# mesure___acquisition.net
KiCad netlist of a schematic drawn in Altium Designer
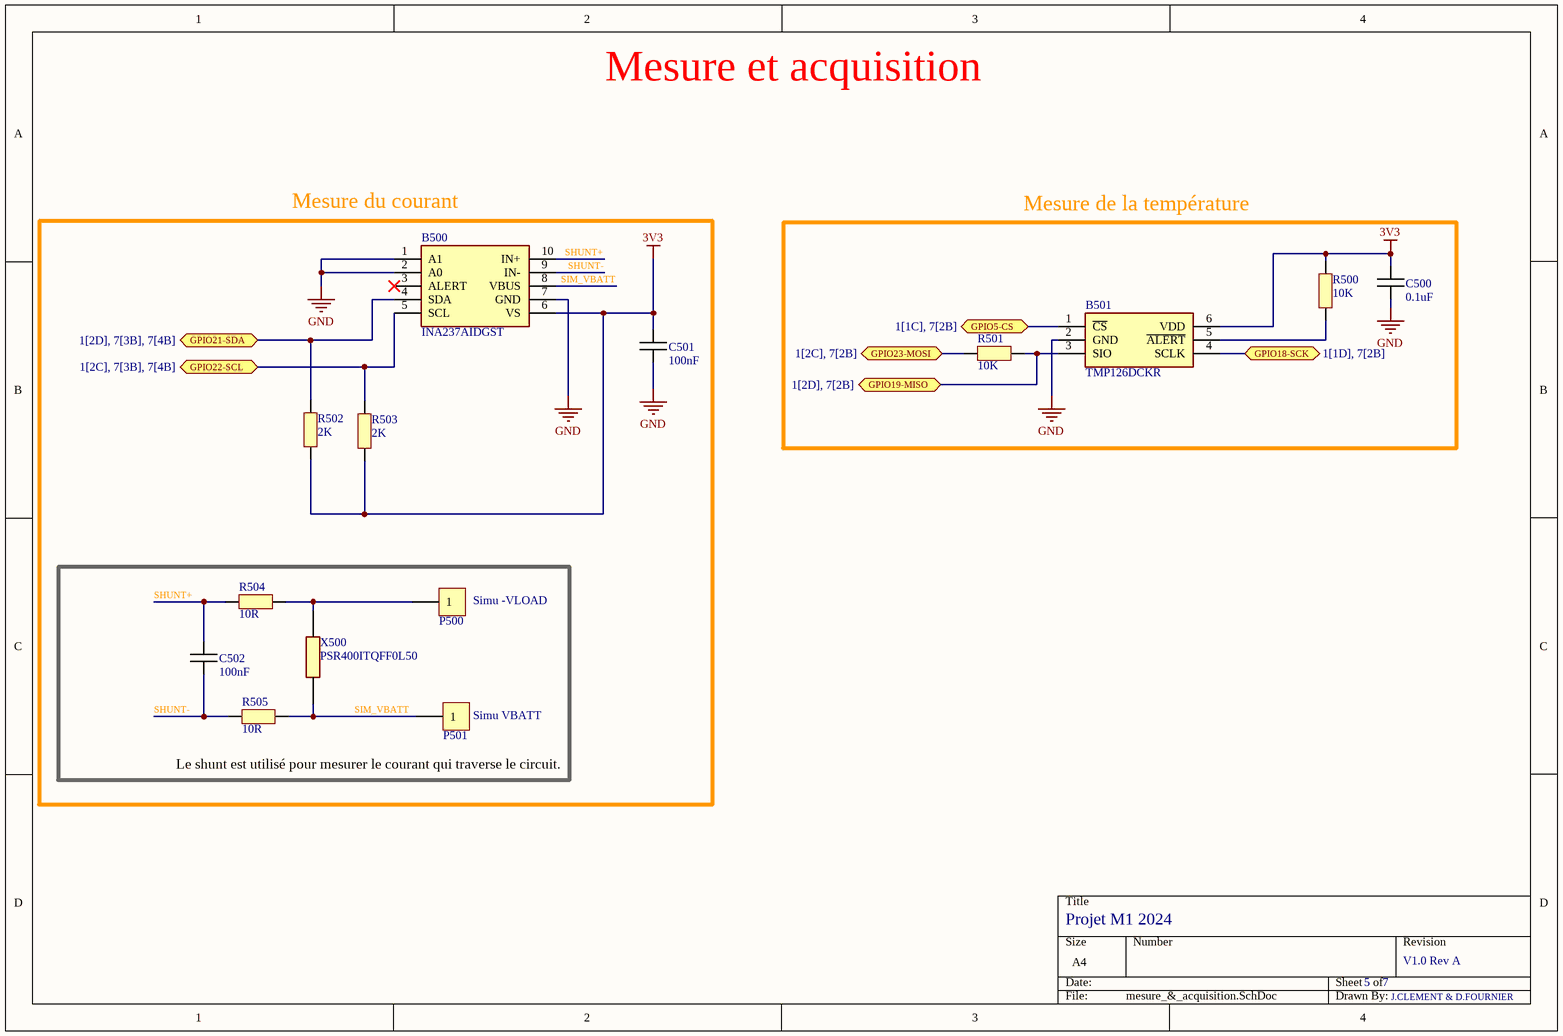
[diagram p0: mesure_&_acquisition.SchDoc]

(export (version "E")
  (design (tool "Eeschema 10.0.6"))
  (components
    (comp (ref "B500")
      (value "INA237AIDGST")
      (footprint "SOP50P490X110-10N")
      (fields (field (name "MOUSER PART NUMBER") "595-INA237AIDGST"))
      (libsource (lib "SCHLibrary") (part "INA237AIDGST"))
    )
    (comp (ref "B501")
      (value "TMP126DCKR")
      (footprint "SOT65P210X110-6N")
      (fields (field (name "MOUSER PART NUMBER") "595-TMP126DCKR"))
      (libsource (lib "SCHLibrary") (part "TMP126DCKR"))
    )
    (comp (ref "C500")
      (value "0.1uF")
      (footprint "CAPA_0603")
      (libsource (lib "SCHLibrary") (part "Capacitor"))
    )
    (comp (ref "C501")
      (value "100nF")
      (footprint "CAPA_0603")
      (libsource (lib "SCHLibrary") (part "Capacitor"))
    )
    (comp (ref "C502")
      (value "100nF")
      (footprint "CAPA_0603")
      (libsource (lib "SCHLibrary") (part "Capacitor"))
    )
    (comp (ref "P500")
      (value "Plage CMS 10x5")
      (footprint "Plage CMS 10x5")
      (description "Plage de report CMS 10x5mm")
      (libsource (lib "SCHLibrary") (part "Plage CMS 10x5"))
    )
    (comp (ref "P501")
      (value "Plage CMS 10x5")
      (footprint "Plage CMS 10x5")
      (description "Plage de report CMS 10x5mm")
      (libsource (lib "SCHLibrary") (part "Plage CMS 10x5"))
    )
    (comp (ref "R500") (value "10K") (footprint "RES_0603") (libsource (lib "SCHLibrary") (part "Resistor")))
    (comp (ref "R501") (value "10K") (footprint "RES_0603") (libsource (lib "") (part "Resistor_1")))
    (comp (ref "R502") (value "2K") (footprint "RES_0603") (libsource (lib "SCHLibrary") (part "Resistor")))
    (comp (ref "R503") (value "2K") (footprint "RES_0603") (libsource (lib "SCHLibrary") (part "Resistor")))
    (comp (ref "R504") (value "10R") (footprint "RES_0603") (libsource (lib "") (part "Resistor_1")))
    (comp (ref "R505") (value "10R") (footprint "RES_0603") (libsource (lib "") (part "Resistor_1")))
    (comp (ref "X500")
      (value "PSR400ITQFF0L50")
      (footprint "RESC10052X200N")
      (fields (field (name "MOUSER PART NUMBER") "755-PSR400ITQFF0L50"))
      (libsource (lib "SCHLibrary") (part "PSR400ITQFF0L50"))
    )
  )
  (nets
    (net (code "1") (name "/GPIO5-CS") (class "Default")
      (node (ref "B501") (pin "1") (pinfunction "~{CS}_1") (pintype "passive"))
    )
    (net (code "2") (name "/GPIO18-SCK") (class "Default")
      (node (ref "B501") (pin "4") (pinfunction "SCLK_4") (pintype "passive"))
    )
    (net (code "3") (name "/GPIO19-MISO") (class "Default")
      (node (ref "B501") (pin "3") (pinfunction "SIO_3") (pintype "passive"))
      (node (ref "R501") (pin "2") (pinfunction "2_2") (pintype "passive"))
    )
    (net (code "4") (name "/GPIO21-SDA") (class "Default")
      (node (ref "B500") (pin "4") (pinfunction "SDA_4") (pintype "passive"))
      (node (ref "R502") (pin "2") (pinfunction "2_2") (pintype "passive"))
    )
    (net (code "5") (name "/GPIO22-SCL") (class "Default")
      (node (ref "B500") (pin "5") (pinfunction "SCL_5") (pintype "passive"))
      (node (ref "R503") (pin "2") (pinfunction "2_2") (pintype "passive"))
    )
    (net (code "6") (name "/GPIO23-MOSI") (class "Default")
      (node (ref "R501") (pin "1") (pinfunction "1_1") (pintype "passive"))
    )
    (net (code "7") (name "/SHUNT+") (class "Default")
      (node (ref "B500") (pin "10") (pinfunction "IN+_10") (pintype "passive"))
      (node (ref "C502") (pin "1") (pinfunction "1_1") (pintype "passive"))
      (node (ref "R504") (pin "1") (pinfunction "1_1") (pintype "passive"))
    )
    (net (code "8") (name "/SHUNT-") (class "Default")
      (node (ref "B500") (pin "9") (pinfunction "IN-_9") (pintype "passive"))
      (node (ref "C502") (pin "2") (pinfunction "2_2") (pintype "passive"))
      (node (ref "R505") (pin "1") (pinfunction "1_1") (pintype "passive"))
    )
    (net (code "9") (name "/SIM_VBATT") (class "Default")
      (node (ref "B500") (pin "8") (pinfunction "VBUS_8") (pintype "passive"))
      (node (ref "P501") (pin "1") (pinfunction "1_1") (pintype "passive"))
      (node (ref "R505") (pin "2") (pinfunction "2_2") (pintype "passive"))
      (node (ref "X500") (pin "1") (pinfunction "1_1") (pintype "passive"))
    )
    (net (code "10") (name "3V3") (class "Default")
      (node (ref "B500") (pin "6") (pinfunction "VS_6") (pintype "passive"))
      (node (ref "B501") (pin "6") (pinfunction "VDD_6") (pintype "passive"))
      (node (ref "C500") (pin "1") (pinfunction "1_1") (pintype "passive"))
      (node (ref "C501") (pin "1") (pinfunction "1_1") (pintype "passive"))
      (node (ref "R500") (pin "2") (pinfunction "2_2") (pintype "passive"))
      (node (ref "R502") (pin "1") (pinfunction "1_1") (pintype "passive"))
      (node (ref "R503") (pin "1") (pinfunction "1_1") (pintype "passive"))
    )
    (net (code "11") (name "GND") (class "Default")
      (node (ref "B500") (pin "1") (pinfunction "A1_1") (pintype "passive"))
      (node (ref "B500") (pin "2") (pinfunction "A0_2") (pintype "passive"))
      (node (ref "B500") (pin "7") (pinfunction "GND_7") (pintype "passive"))
      (node (ref "B501") (pin "2") (pinfunction "GND_2") (pintype "passive"))
      (node (ref "C500") (pin "2") (pinfunction "2_2") (pintype "passive"))
      (node (ref "C501") (pin "2") (pinfunction "2_2") (pintype "passive"))
    )
    (net (code "12") (name "Net-(B501-~{ALERT})") (class "Default")
      (node (ref "B501") (pin "5") (pinfunction "~{ALERT}_5") (pintype "passive"))
      (node (ref "R500") (pin "1") (pinfunction "1_1") (pintype "passive"))
    )
    (net (code "13") (name "Net-(P500-Pad1)") (class "Default")
      (node (ref "P500") (pin "1") (pinfunction "1_1") (pintype "passive"))
      (node (ref "R504") (pin "2") (pinfunction "2_2") (pintype "passive"))
      (node (ref "X500") (pin "2") (pinfunction "2_2") (pintype "passive"))
    )
    (net (code "14") (name "unconnected-(B500-ALERT-Pad3)") (class "Default")
      (node (ref "B500") (pin "3") (pinfunction "ALERT_3") (pintype "passive+no_connect"))
    )
  )
)
